# Blueshift_V4.net
KiCad netlist of a schematic drawn in EAGLE
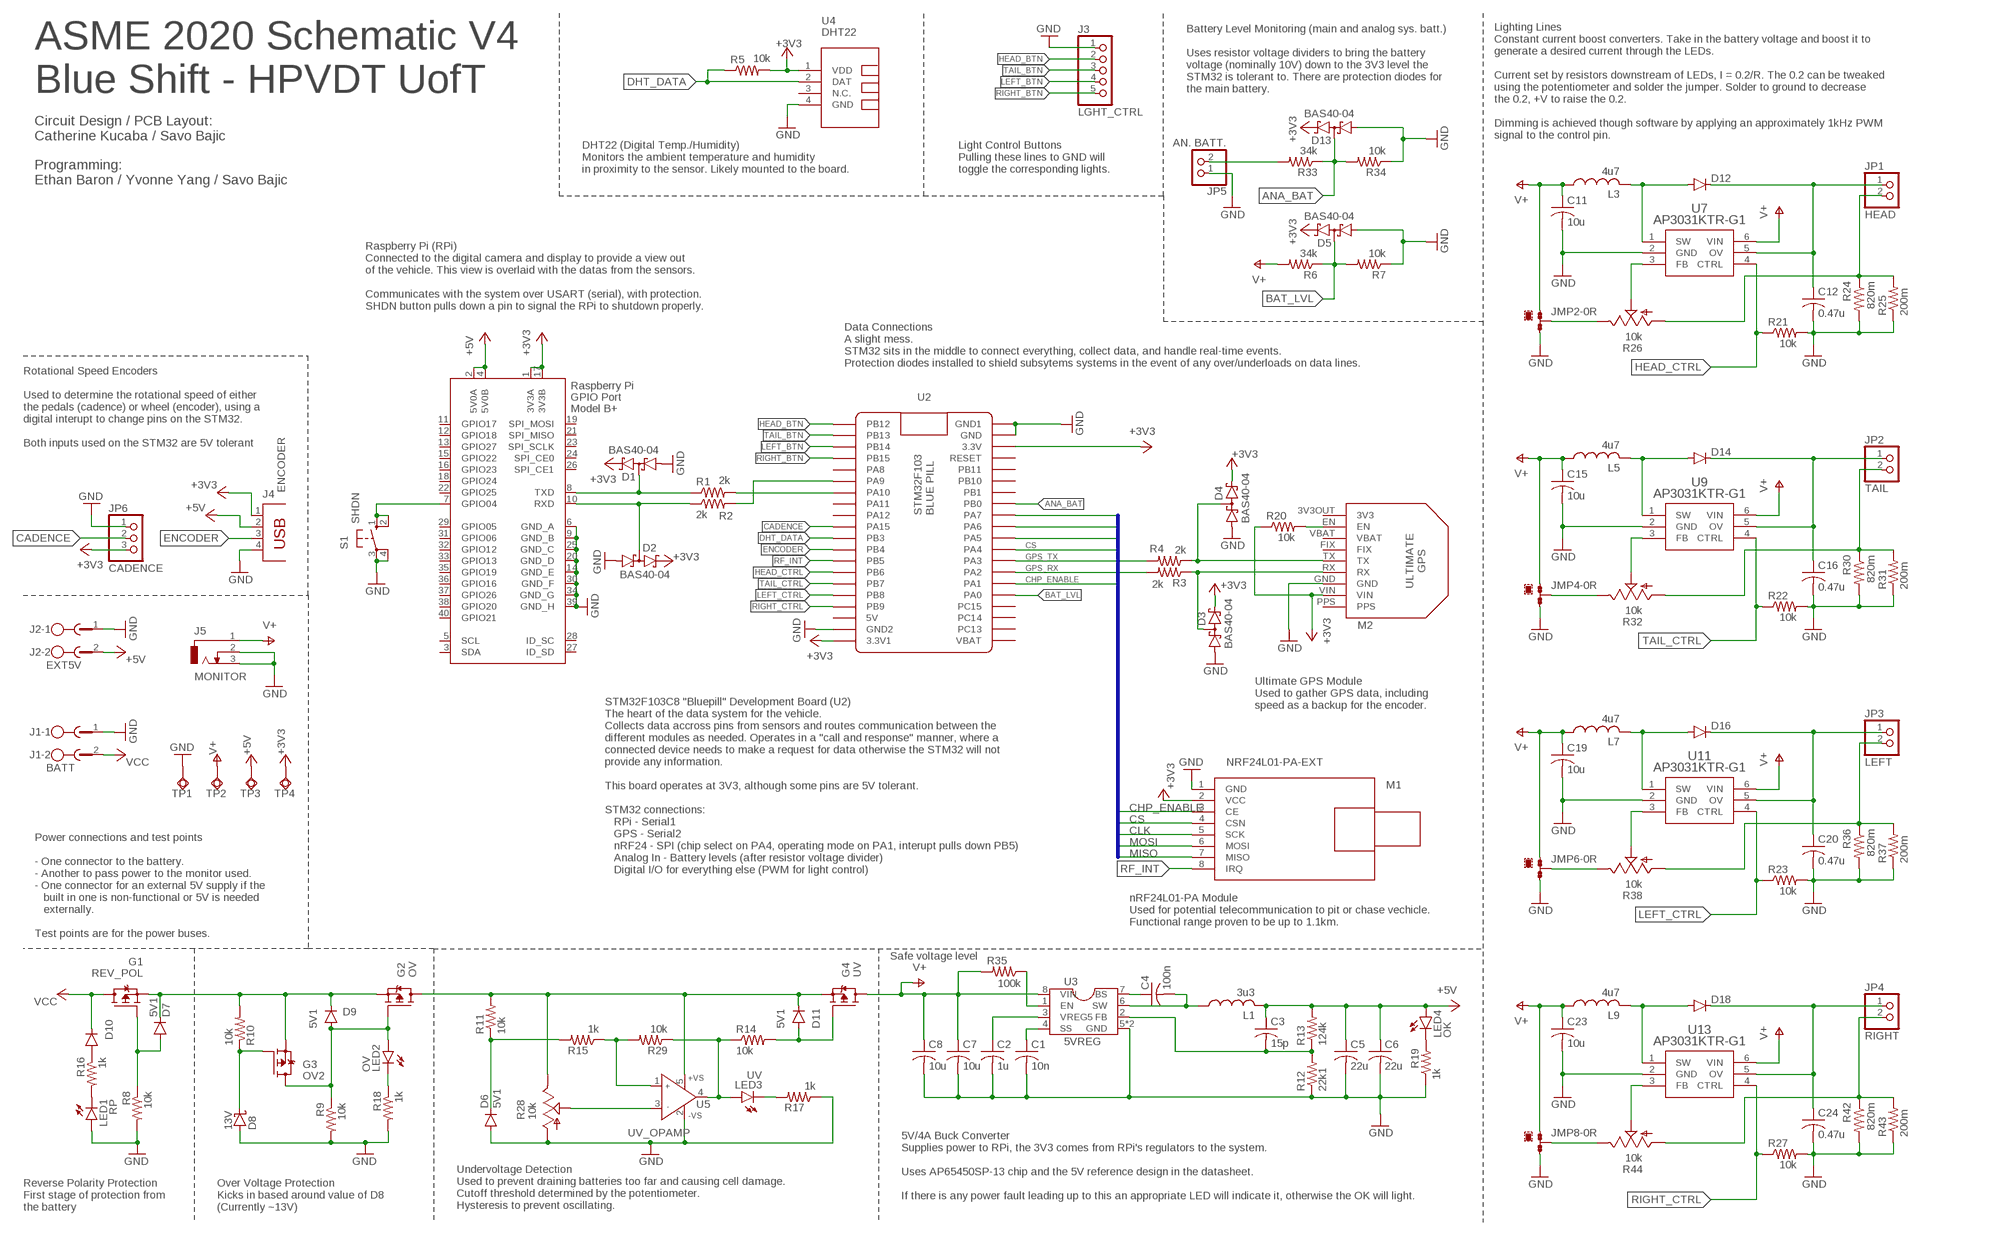
[diagram p0: schematic, sheet 1]

(export (version "E")
  (design (tool "Eeschema 10.0.6"))
  (components
    (comp (ref "C1")
      (value "10n")
      (footprint "eagle-import:C0402")
      (libsource (lib "eagle-import") (part "C-USC0402"))
    )
    (comp (ref "C2")
      (value "1u")
      (footprint "eagle-import:C0402")
      (libsource (lib "eagle-import") (part "C-USC0402"))
    )
    (comp (ref "C3")
      (value "15p")
      (footprint "eagle-import:C0402")
      (libsource (lib "eagle-import") (part "C-USC0402"))
    )
    (comp (ref "C4")
      (value "100n")
      (footprint "eagle-import:C0402")
      (libsource (lib "eagle-import") (part "C-USC0402"))
    )
    (comp (ref "C5")
      (value "22u")
      (footprint "eagle-import:C0805")
      (libsource (lib "eagle-import") (part "C-USC0805"))
    )
    (comp (ref "C6")
      (value "22u")
      (footprint "eagle-import:C0805")
      (libsource (lib "eagle-import") (part "C-USC0805"))
    )
    (comp (ref "C7")
      (value "10u")
      (footprint "eagle-import:C0805")
      (libsource (lib "eagle-import") (part "C-USC0805"))
    )
    (comp (ref "C8")
      (value "10u")
      (footprint "eagle-import:C0805")
      (libsource (lib "eagle-import") (part "C-USC0805"))
    )
    (comp (ref "C11")
      (value "10u")
      (footprint "eagle-import:C1206K")
      (libsource (lib "eagle-import") (part "C-USC1206K"))
    )
    (comp (ref "C12")
      (value "0.47u")
      (footprint "eagle-import:C1206K")
      (libsource (lib "eagle-import") (part "C-USC1206K"))
    )
    (comp (ref "C15")
      (value "10u")
      (footprint "eagle-import:C1206K")
      (libsource (lib "eagle-import") (part "C-USC1206K"))
    )
    (comp (ref "C16")
      (value "0.47u")
      (footprint "eagle-import:C1206K")
      (libsource (lib "eagle-import") (part "C-USC1206K"))
    )
    (comp (ref "C19")
      (value "10u")
      (footprint "eagle-import:C1206K")
      (libsource (lib "eagle-import") (part "C-USC1206K"))
    )
    (comp (ref "C20")
      (value "0.47u")
      (footprint "eagle-import:C1206K")
      (libsource (lib "eagle-import") (part "C-USC1206K"))
    )
    (comp (ref "C23")
      (value "10u")
      (footprint "eagle-import:C1206K")
      (libsource (lib "eagle-import") (part "C-USC1206K"))
    )
    (comp (ref "C24")
      (value "0.47u")
      (footprint "eagle-import:C1206K")
      (libsource (lib "eagle-import") (part "C-USC1206K"))
    )
    (comp (ref "D1")
      (value "BAS40-04")
      (footprint "eagle-import:SOT23")
      (libsource (lib "eagle-import") (part "BAS40-04"))
    )
    (comp (ref "D2")
      (value "BAS40-04")
      (footprint "eagle-import:SOT23")
      (libsource (lib "eagle-import") (part "BAS40-04"))
    )
    (comp (ref "D3")
      (value "BAS40-04")
      (footprint "eagle-import:SOT23")
      (libsource (lib "eagle-import") (part "BAS40-04"))
    )
    (comp (ref "D4")
      (value "BAS40-04")
      (footprint "eagle-import:SOT23")
      (libsource (lib "eagle-import") (part "BAS40-04"))
    )
    (comp (ref "D5")
      (value "BAS40-04")
      (footprint "eagle-import:SOT23")
      (libsource (lib "eagle-import") (part "BAS40-04"))
    )
    (comp (ref "D6")
      (value "5V1")
      (footprint "eagle-import:SOD323-R")
      (libsource (lib "eagle-import") (part "DIODE-SOD323-R"))
    )
    (comp (ref "D7")
      (value "5V1")
      (footprint "eagle-import:SOD323-R")
      (libsource (lib "eagle-import") (part "DIODE-SOD323-R"))
    )
    (comp (ref "D8")
      (value "13V")
      (footprint "eagle-import:SOT23")
      (libsource (lib "eagle-import") (part "BAS70"))
    )
    (comp (ref "D9")
      (value "5V1")
      (footprint "eagle-import:SOD323-R")
      (libsource (lib "eagle-import") (part "DIODE-SOD323-R"))
    )
    (comp (ref "D10")
      (value "DIODE-SOD80C")
      (footprint "eagle-import:SOD80C")
      (libsource (lib "eagle-import") (part "DIODE-SOD80C"))
    )
    (comp (ref "D11")
      (value "5V1")
      (footprint "eagle-import:SOD323-R")
      (libsource (lib "eagle-import") (part "DIODE-SOD323-R"))
    )
    (comp (ref "D12")
      (value "DIODE-DO-214AC")
      (footprint "eagle-import:DO-214AC")
      (libsource (lib "eagle-import") (part "DIODE-DO-214AC"))
    )
    (comp (ref "D13")
      (value "BAS40-04")
      (footprint "eagle-import:SOT23")
      (libsource (lib "eagle-import") (part "BAS40-04"))
    )
    (comp (ref "D14")
      (value "DIODE-DO-214AC")
      (footprint "eagle-import:DO-214AC")
      (libsource (lib "eagle-import") (part "DIODE-DO-214AC"))
    )
    (comp (ref "D16")
      (value "DIODE-DO-214AC")
      (footprint "eagle-import:DO-214AC")
      (libsource (lib "eagle-import") (part "DIODE-DO-214AC"))
    )
    (comp (ref "D18")
      (value "DIODE-DO-214AC")
      (footprint "eagle-import:DO-214AC")
      (libsource (lib "eagle-import") (part "DIODE-DO-214AC"))
    )
    (comp (ref "G1")
      (value "REV_POL")
      (footprint "eagle-import:TSOP-6")
      (libsource (lib "eagle-import") (part "SI3493DDV-T1-GE3"))
    )
    (comp (ref "G2")
      (value "OV")
      (footprint "eagle-import:TSOP-6")
      (libsource (lib "eagle-import") (part "SI3493DDV-T1-GE3"))
    )
    (comp (ref "G3")
      (value "OV2")
      (footprint "eagle-import:TSOP-6")
      (libsource (lib "eagle-import") (part "SI3493DDV-T1-GE3"))
    )
    (comp (ref "G4")
      (value "UV")
      (footprint "eagle-import:TSOP-6")
      (libsource (lib "eagle-import") (part "SI3493DDV-T1-GE3"))
    )
    (comp (ref "J1")
      (value "BATT")
      (footprint "eagle-import:MSTBV2")
      (libsource (lib "eagle-import") (part "MST2V"))
    )
    (comp (ref "J2")
      (value "EXT5V")
      (footprint "eagle-import:MSTBV2")
      (libsource (lib "eagle-import") (part "MST2V"))
    )
    (comp (ref "J3")
      (value "LGHT_CTRL")
      (footprint "eagle-import:1X05")
      (libsource (lib "eagle-import") (part "PINHD-1X5"))
    )
    (comp (ref "J4")
      (value "ENCODER")
      (footprint "eagle-import:PN87520")
      (libsource (lib "eagle-import") (part "PN87520"))
    )
    (comp (ref "J5")
      (value "MONITOR")
      (footprint "eagle-import:DCJ0303")
      (libsource (lib "eagle-import") (part "DCJ0303"))
    )
    (comp (ref "JMP2")
      (value "0R-JUMPA")
      (footprint "eagle-import:A0R-JMP")
      (libsource (lib "eagle-import") (part "0R-JUMPA"))
    )
    (comp (ref "JMP4")
      (value "0R-JUMPA")
      (footprint "eagle-import:A0R-JMP")
      (libsource (lib "eagle-import") (part "0R-JUMPA"))
    )
    (comp (ref "JMP6")
      (value "0R-JUMPA")
      (footprint "eagle-import:A0R-JMP")
      (libsource (lib "eagle-import") (part "0R-JUMPA"))
    )
    (comp (ref "JMP8")
      (value "0R-JUMPA")
      (footprint "eagle-import:A0R-JMP")
      (libsource (lib "eagle-import") (part "0R-JUMPA"))
    )
    (comp (ref "JP1")
      (value "HEAD")
      (footprint "eagle-import:1X02")
      (libsource (lib "eagle-import") (part "PINHD-1X2"))
    )
    (comp (ref "JP2")
      (value "TAIL")
      (footprint "eagle-import:1X02")
      (libsource (lib "eagle-import") (part "PINHD-1X2"))
    )
    (comp (ref "JP3")
      (value "LEFT")
      (footprint "eagle-import:1X02")
      (libsource (lib "eagle-import") (part "PINHD-1X2"))
    )
    (comp (ref "JP4")
      (value "RIGHT")
      (footprint "eagle-import:1X02")
      (libsource (lib "eagle-import") (part "PINHD-1X2"))
    )
    (comp (ref "JP5")
      (value "AN. BATT.")
      (footprint "eagle-import:1X02")
      (libsource (lib "eagle-import") (part "PINHD-1X2"))
    )
    (comp (ref "JP6")
      (value "CADENCE")
      (footprint "eagle-import:1X03")
      (libsource (lib "eagle-import") (part "PINHD-1X3"))
    )
    (comp (ref "L1")
      (value "3u3")
      (footprint "eagle-import:SDES064T")
      (libsource (lib "eagle-import") (part "SDES064T-3R3MS"))
    )
    (comp (ref "L3")
      (value "4u7")
      (footprint "eagle-import:INDDFN600X600X280-2N")
      (libsource (lib "eagle-import") (part "NR6028NR6028"))
    )
    (comp (ref "L5")
      (value "4u7")
      (footprint "eagle-import:INDDFN600X600X280-2N")
      (libsource (lib "eagle-import") (part "NR6028NR6028"))
    )
    (comp (ref "L7")
      (value "4u7")
      (footprint "eagle-import:INDDFN600X600X280-2N")
      (libsource (lib "eagle-import") (part "NR6028NR6028"))
    )
    (comp (ref "L9")
      (value "4u7")
      (footprint "eagle-import:INDDFN600X600X280-2N")
      (libsource (lib "eagle-import") (part "NR6028NR6028"))
    )
    (comp (ref "LED1")
      (value "RP")
      (footprint "eagle-import:SML0805")
      (libsource (lib "eagle-import") (part "LEDSML0805"))
    )
    (comp (ref "LED2")
      (value "OV")
      (footprint "eagle-import:SML0805")
      (libsource (lib "eagle-import") (part "LEDSML0805"))
    )
    (comp (ref "LED3")
      (value "UV")
      (footprint "eagle-import:SML0805")
      (libsource (lib "eagle-import") (part "LEDSML0805"))
    )
    (comp (ref "LED4")
      (value "OK")
      (footprint "eagle-import:SML0805")
      (libsource (lib "eagle-import") (part "LEDSML0805"))
    )
    (comp (ref "M1")
      (value "NRF24L01-PA-EXT")
      (footprint "eagle-import:WIRELESS-NRF24L01-PA-EXT")
      (libsource (lib "eagle-import") (part "WIRELESS-NRF24L01-PA-EXT"))
    )
    (comp (ref "M2")
      (value "ULTIMATE-GPS")
      (footprint "eagle-import:ULTIMATE_GPS")
      (libsource (lib "eagle-import") (part "ULTIMATE-GPS"))
    )
    (comp (ref "R1")
      (value "2k")
      (footprint "eagle-import:R0402")
      (libsource (lib "eagle-import") (part "R-US_R0402"))
    )
    (comp (ref "R2")
      (value "2k")
      (footprint "eagle-import:R0402")
      (libsource (lib "eagle-import") (part "R-US_R0402"))
    )
    (comp (ref "R3")
      (value "2k")
      (footprint "eagle-import:R0402")
      (libsource (lib "eagle-import") (part "R-US_R0402"))
    )
    (comp (ref "R4")
      (value "2k")
      (footprint "eagle-import:R0402")
      (libsource (lib "eagle-import") (part "R-US_R0402"))
    )
    (comp (ref "R5")
      (value "10k")
      (footprint "eagle-import:R0402")
      (libsource (lib "eagle-import") (part "R-US_R0402"))
    )
    (comp (ref "R6")
      (value "34k")
      (footprint "eagle-import:R0402")
      (libsource (lib "eagle-import") (part "R-US_R0402"))
    )
    (comp (ref "R7")
      (value "10k")
      (footprint "eagle-import:R0402")
      (libsource (lib "eagle-import") (part "R-US_R0402"))
    )
    (comp (ref "R8")
      (value "10k")
      (footprint "eagle-import:R0402")
      (libsource (lib "eagle-import") (part "R-US_R0402"))
    )
    (comp (ref "R9")
      (value "10k")
      (footprint "eagle-import:R0402")
      (libsource (lib "eagle-import") (part "R-US_R0402"))
    )
    (comp (ref "R10")
      (value "10k")
      (footprint "eagle-import:R0402")
      (libsource (lib "eagle-import") (part "R-US_R0402"))
    )
    (comp (ref "R11")
      (value "10k")
      (footprint "eagle-import:R0402")
      (libsource (lib "eagle-import") (part "R-US_R0402"))
    )
    (comp (ref "R12")
      (value "22k1")
      (footprint "eagle-import:R0402")
      (libsource (lib "eagle-import") (part "R-US_R0402"))
    )
    (comp (ref "R13")
      (value "124k")
      (footprint "eagle-import:R0402")
      (libsource (lib "eagle-import") (part "R-US_R0402"))
    )
    (comp (ref "R14")
      (value "10k")
      (footprint "eagle-import:R0402")
      (libsource (lib "eagle-import") (part "R-US_R0402"))
    )
    (comp (ref "R15")
      (value "1k")
      (footprint "eagle-import:R0402")
      (libsource (lib "eagle-import") (part "R-US_R0402"))
    )
    (comp (ref "R16")
      (value "1k")
      (footprint "eagle-import:R0402")
      (libsource (lib "eagle-import") (part "R-US_R0402"))
    )
    (comp (ref "R17")
      (value "1k")
      (footprint "eagle-import:R0402")
      (libsource (lib "eagle-import") (part "R-US_R0402"))
    )
    (comp (ref "R18")
      (value "1k")
      (footprint "eagle-import:R0402")
      (libsource (lib "eagle-import") (part "R-US_R0402"))
    )
    (comp (ref "R19")
      (value "1k")
      (footprint "eagle-import:R0402")
      (libsource (lib "eagle-import") (part "R-US_R0402"))
    )
    (comp (ref "R20")
      (value "10k")
      (footprint "eagle-import:R0402")
      (libsource (lib "eagle-import") (part "R-US_R0402"))
    )
    (comp (ref "R21")
      (value "10k")
      (footprint "eagle-import:R0402")
      (libsource (lib "eagle-import") (part "R-US_R0402"))
    )
    (comp (ref "R22")
      (value "10k")
      (footprint "eagle-import:R0402")
      (libsource (lib "eagle-import") (part "R-US_R0402"))
    )
    (comp (ref "R23")
      (value "10k")
      (footprint "eagle-import:R0402")
      (libsource (lib "eagle-import") (part "R-US_R0402"))
    )
    (comp (ref "R24")
      (value "820m")
      (footprint "eagle-import:R0603")
      (libsource (lib "eagle-import") (part "R-US_R0603"))
    )
    (comp (ref "R25")
      (value "200m")
      (footprint "eagle-import:R0805")
      (libsource (lib "eagle-import") (part "R-US_R0805"))
    )
    (comp (ref "R26")
      (value "10k")
      (footprint "eagle-import:RJ9W")
      (libsource (lib "eagle-import") (part "TRIM_US-RJ9W"))
    )
    (comp (ref "R27")
      (value "10k")
      (footprint "eagle-import:R0402")
      (libsource (lib "eagle-import") (part "R-US_R0402"))
    )
    (comp (ref "R28")
      (value "10k")
      (footprint "eagle-import:RJ9W")
      (libsource (lib "eagle-import") (part "TRIM_US-RJ9W"))
    )
    (comp (ref "R29")
      (value "10k")
      (footprint "eagle-import:R0402")
      (libsource (lib "eagle-import") (part "R-US_R0402"))
    )
    (comp (ref "R30")
      (value "820m")
      (footprint "eagle-import:R0603")
      (libsource (lib "eagle-import") (part "R-US_R0603"))
    )
    (comp (ref "R31")
      (value "200m")
      (footprint "eagle-import:R0805")
      (libsource (lib "eagle-import") (part "R-US_R0805"))
    )
    (comp (ref "R32")
      (value "10k")
      (footprint "eagle-import:RJ9W")
      (libsource (lib "eagle-import") (part "TRIM_US-RJ9W"))
    )
    (comp (ref "R33")
      (value "34k")
      (footprint "eagle-import:R0402")
      (libsource (lib "eagle-import") (part "R-US_R0402"))
    )
    (comp (ref "R34")
      (value "10k")
      (footprint "eagle-import:R0402")
      (libsource (lib "eagle-import") (part "R-US_R0402"))
    )
    (comp (ref "R35")
      (value "100k")
      (footprint "eagle-import:R0402")
      (libsource (lib "eagle-import") (part "R-US_R0402"))
    )
    (comp (ref "R36")
      (value "820m")
      (footprint "eagle-import:R0603")
      (libsource (lib "eagle-import") (part "R-US_R0603"))
    )
    (comp (ref "R37")
      (value "200m")
      (footprint "eagle-import:R0805")
      (libsource (lib "eagle-import") (part "R-US_R0805"))
    )
    (comp (ref "R38")
      (value "10k")
      (footprint "eagle-import:RJ9W")
      (libsource (lib "eagle-import") (part "TRIM_US-RJ9W"))
    )
    (comp (ref "R42")
      (value "820m")
      (footprint "eagle-import:R0603")
      (libsource (lib "eagle-import") (part "R-US_R0603"))
    )
    (comp (ref "R43")
      (value "200m")
      (footprint "eagle-import:R0805")
      (libsource (lib "eagle-import") (part "R-US_R0805"))
    )
    (comp (ref "R44")
      (value "10k")
      (footprint "eagle-import:RJ9W")
      (libsource (lib "eagle-import") (part "TRIM_US-RJ9W"))
    )
    (comp (ref "S1")
      (value "SHDN")
      (footprint "eagle-import:B3F-10XX")
      (fields (field (name "MPN") "B3F-1000"))
      (libsource (lib "eagle-import") (part "10-XX"))
    )
    (comp (ref "TP1")
      (value "TPSQTP20SQ")
      (footprint "eagle-import:TP20SQ")
      (libsource (lib "eagle-import") (part "TPSQTP20SQ"))
    )
    (comp (ref "TP2")
      (value "TPSQTP20R")
      (footprint "eagle-import:TP20R")
      (libsource (lib "eagle-import") (part "TPSQTP20R"))
    )
    (comp (ref "TP3")
      (value "TPSQTP20R")
      (footprint "eagle-import:TP20R")
      (libsource (lib "eagle-import") (part "TPSQTP20R"))
    )
    (comp (ref "TP4")
      (value "TPSQTP20R")
      (footprint "eagle-import:TP20R")
      (libsource (lib "eagle-import") (part "TPSQTP20R"))
    )
    (comp (ref "U1")
      (value "RASPI_HAT")
      (footprint "eagle-import:RASPI_BOARD_B+HAT_CF")
      (libsource (lib "eagle-import") (part "RASPI_HAT"))
    )
    (comp (ref "U2")
      (value "BLUEPILL")
      (footprint "eagle-import:BLUE_PILL")
      (libsource (lib "eagle-import") (part "BLUE_PILL"))
    )
    (comp (ref "U3")
      (value "5VREG")
      (footprint "eagle-import:SO-8EP")
      (libsource (lib "eagle-import") (part "AP65450SP-13"))
    )
    (comp (ref "U4")
      (value "DHT22")
      (footprint "eagle-import:TEMP-HUM-SENSOR-DHT22")
      (libsource (lib "eagle-import") (part "TEMP-HUM-SENSOR-DHT22"))
    )
    (comp (ref "U5")
      (value "UV_OPAMP")
      (footprint "eagle-import:SOT-753")
      (libsource (lib "eagle-import") (part "TA75S558F,LF"))
    )
    (comp (ref "U7")
      (value "AP3031KTR-G1")
      (footprint "eagle-import:SOT23-6")
      (fields (field (name "MANUFACTURER_PART_NUMBER") "AP3031KTRG1"))
      (libsource (lib "eagle-import") (part "AP3031KTR-G1"))
    )
    (comp (ref "U9")
      (value "AP3031KTR-G1")
      (footprint "eagle-import:SOT23-6")
      (fields (field (name "MANUFACTURER_PART_NUMBER") "AP3031KTRG1"))
      (libsource (lib "eagle-import") (part "AP3031KTR-G1"))
    )
    (comp (ref "U11")
      (value "AP3031KTR-G1")
      (footprint "eagle-import:SOT23-6")
      (fields (field (name "MANUFACTURER_PART_NUMBER") "AP3031KTRG1"))
      (libsource (lib "eagle-import") (part "AP3031KTR-G1"))
    )
    (comp (ref "U13")
      (value "AP3031KTR-G1")
      (footprint "eagle-import:SOT23-6")
      (fields (field (name "MANUFACTURER_PART_NUMBER") "AP3031KTRG1"))
      (libsource (lib "eagle-import") (part "AP3031KTR-G1"))
    )
  )
  (nets
    (net (code "1") (name "+3V3") (class "Default")
      (node (ref "D1") (pin "2") (pinfunction "C2_2") (pintype "passive"))
      (node (ref "D13") (pin "2") (pinfunction "C2_2") (pintype "passive"))
      (node (ref "D2") (pin "2") (pinfunction "C2_2") (pintype "passive"))
      (node (ref "D3") (pin "2") (pinfunction "C2_2") (pintype "passive"))
      (node (ref "D4") (pin "2") (pinfunction "C2_2") (pintype "passive"))
      (node (ref "D5") (pin "2") (pinfunction "C2_2") (pintype "passive"))
      (node (ref "J4") (pin "1") (pinfunction "1_1") (pintype "passive"))
      (node (ref "JP6") (pin "3") (pinfunction "3_3") (pintype "passive"))
      (node (ref "M1") (pin "2") (pinfunction "VCC_2") (pintype "power_in"))
      (node (ref "M2") (pin "VIN") (pinfunction "VIN_VIN") (pintype "power_in"))
      (node (ref "R20") (pin "1") (pinfunction "1_1") (pintype "passive"))
      (node (ref "R5") (pin "2") (pinfunction "2_2") (pintype "passive"))
      (node (ref "TP4") (pin "TP") (pinfunction "TP_TP") (pintype "input"))
      (node (ref "U1") (pin "1") (pinfunction "3V3A_1") (pintype "power_in"))
      (node (ref "U1") (pin "17") (pinfunction "3V3B_17") (pintype "power_in"))
      (node (ref "U2") (pin "P$20") (pinfunction "3.3V1_P$20") (pintype "bidirectional"))
      (node (ref "U2") (pin "P$23") (pinfunction "3.3V_P$23") (pintype "bidirectional"))
      (node (ref "U4") (pin "1") (pinfunction "VDD_1") (pintype "power_in"))
    )
    (net (code "2") (name "+5V") (class "Default")
      (node (ref "C3") (pin "1") (pinfunction "1_1") (pintype "passive"))
      (node (ref "C5") (pin "1") (pinfunction "1_1") (pintype "passive"))
      (node (ref "C6") (pin "1") (pinfunction "1_1") (pintype "passive"))
      (node (ref "J2") (pin "2") (pinfunction "1_2") (pintype "passive"))
      (node (ref "J4") (pin "2") (pinfunction "2_2") (pintype "passive"))
      (node (ref "L1") (pin "2") (pinfunction "2_2") (pintype "passive"))
      (node (ref "LED4") (pin "A") (pinfunction "A_A") (pintype "passive"))
      (node (ref "R13") (pin "2") (pinfunction "2_2") (pintype "passive"))
      (node (ref "TP3") (pin "TP") (pinfunction "TP_TP") (pintype "input"))
      (node (ref "U1") (pin "2") (pinfunction "5V0A_2") (pintype "power_in"))
      (node (ref "U1") (pin "4") (pinfunction "5V0B_4") (pintype "power_in"))
    )
    (net (code "3") (name "/CHP_ENABLE") (class "Default")
      (node (ref "M1") (pin "3") (pinfunction "CE_3") (pintype "bidirectional"))
      (node (ref "U2") (pin "P$35") (pinfunction "PA1_P$35") (pintype "bidirectional"))
    )
    (net (code "4") (name "/CLK") (class "Default")
      (node (ref "M1") (pin "5") (pinfunction "SCK_5") (pintype "bidirectional"))
      (node (ref "U2") (pin "P$31") (pinfunction "PA5_P$31") (pintype "bidirectional"))
    )
    (net (code "5") (name "/CS") (class "Default")
      (node (ref "M1") (pin "4") (pinfunction "CSN_4") (pintype "bidirectional"))
      (node (ref "U2") (pin "P$32") (pinfunction "PA4_P$32") (pintype "bidirectional"))
    )
    (net (code "6") (name "/GPS_RX") (class "Default")
      (node (ref "R3") (pin "2") (pinfunction "2_2") (pintype "passive"))
      (node (ref "U2") (pin "P$34") (pinfunction "PA2_P$34") (pintype "bidirectional"))
    )
    (net (code "7") (name "/GPS_TX") (class "Default")
      (node (ref "R4") (pin "2") (pinfunction "2_2") (pintype "passive"))
      (node (ref "U2") (pin "P$33") (pinfunction "PA3_P$33") (pintype "bidirectional"))
    )
    (net (code "8") (name "/MISO") (class "Default")
      (node (ref "M1") (pin "7") (pinfunction "MISO_7") (pintype "bidirectional"))
      (node (ref "U2") (pin "P$30") (pinfunction "PA6_P$30") (pintype "bidirectional"))
    )
    (net (code "9") (name "/MOSI") (class "Default")
      (node (ref "M1") (pin "6") (pinfunction "MOSI_6") (pintype "bidirectional"))
      (node (ref "U2") (pin "P$29") (pinfunction "PA7_P$29") (pintype "bidirectional"))
    )
    (net (code "10") (name "ANA_BAT") (class "Default")
      (node (ref "D13") (pin "3") (pinfunction "C1A2_3") (pintype "passive"))
      (node (ref "R33") (pin "1") (pinfunction "1_1") (pintype "passive"))
      (node (ref "R34") (pin "2") (pinfunction "2_2") (pintype "passive"))
      (node (ref "U2") (pin "P$28") (pinfunction "PB0_P$28") (pintype "bidirectional"))
    )
    (net (code "11") (name "BAT_LVL") (class "Default")
      (node (ref "D5") (pin "3") (pinfunction "C1A2_3") (pintype "passive"))
      (node (ref "R6") (pin "1") (pinfunction "1_1") (pintype "passive"))
      (node (ref "R7") (pin "2") (pinfunction "2_2") (pintype "passive"))
      (node (ref "U2") (pin "P$36") (pinfunction "PA0_P$36") (pintype "bidirectional"))
    )
    (net (code "12") (name "CADENCE") (class "Default")
      (node (ref "JP6") (pin "2") (pinfunction "2_2") (pintype "passive"))
      (node (ref "U2") (pin "P$10") (pinfunction "PA15_P$10") (pintype "bidirectional"))
    )
    (net (code "13") (name "DHT_DATA") (class "Default")
      (node (ref "R5") (pin "1") (pinfunction "1_1") (pintype "passive"))
      (node (ref "U2") (pin "P$11") (pinfunction "PB3_P$11") (pintype "bidirectional"))
      (node (ref "U4") (pin "2") (pinfunction "DAT_2") (pintype "bidirectional"))
    )
    (net (code "14") (name "ENCODER") (class "Default")
      (node (ref "J4") (pin "3") (pinfunction "3_3") (pintype "passive"))
      (node (ref "U2") (pin "P$12") (pinfunction "PB4_P$12") (pintype "bidirectional"))
    )
    (net (code "15") (name "GND") (class "Default")
      (node (ref "C1") (pin "2") (pinfunction "2_2") (pintype "passive"))
      (node (ref "C11") (pin "2") (pinfunction "2_2") (pintype "passive"))
      (node (ref "C12") (pin "2") (pinfunction "2_2") (pintype "passive"))
      (node (ref "C15") (pin "2") (pinfunction "2_2") (pintype "passive"))
      (node (ref "C16") (pin "2") (pinfunction "2_2") (pintype "passive"))
      (node (ref "C19") (pin "2") (pinfunction "2_2") (pintype "passive"))
      (node (ref "C2") (pin "2") (pinfunction "2_2") (pintype "passive"))
      (node (ref "C20") (pin "2") (pinfunction "2_2") (pintype "passive"))
      (node (ref "C23") (pin "2") (pinfunction "2_2") (pintype "passive"))
      (node (ref "C24") (pin "2") (pinfunction "2_2") (pintype "passive"))
      (node (ref "C5") (pin "2") (pinfunction "2_2") (pintype "passive"))
      (node (ref "C6") (pin "2") (pinfunction "2_2") (pintype "passive"))
      (node (ref "C7") (pin "2") (pinfunction "2_2") (pintype "passive"))
      (node (ref "C8") (pin "2") (pinfunction "2_2") (pintype "passive"))
      (node (ref "D1") (pin "1") (pinfunction "A1_1") (pintype "passive"))
      (node (ref "D13") (pin "1") (pinfunction "A1_1") (pintype "passive"))
      (node (ref "D2") (pin "1") (pinfunction "A1_1") (pintype "passive"))
      (node (ref "D3") (pin "1") (pinfunction "A1_1") (pintype "passive"))
      (node (ref "D4") (pin "1") (pinfunction "A1_1") (pintype "passive"))
      (node (ref "D5") (pin "1") (pinfunction "A1_1") (pintype "passive"))
      (node (ref "D6") (pin "A") (pinfunction "A_A") (pintype "passive"))
      (node (ref "D8") (pin "1") (pinfunction "A_1") (pintype "passive"))
      (node (ref "J1") (pin "1") (pinfunction "1_1") (pintype "passive"))
      (node (ref "J2") (pin "1") (pinfunction "1_1") (pintype "passive"))
      (node (ref "J3") (pin "1") (pinfunction "1_1") (pintype "passive"))
      (node (ref "J4") (pin "4") (pinfunction "4_4") (pintype "passive"))
      (node (ref "J5") (pin "2") (pinfunction "2_2") (pintype "passive"))
      (node (ref "J5") (pin "3") (pinfunction "3_3") (pintype "passive"))
      (node (ref "JMP2") (pin "3") (pinfunction "3_3") (pintype "passive"))
      (node (ref "JMP4") (pin "3") (pinfunction "3_3") (pintype "passive"))
      (node (ref "JMP6") (pin "3") (pinfunction "3_3") (pintype "passive"))
      (node (ref "JMP8") (pin "3") (pinfunction "3_3") (pintype "passive"))
      (node (ref "JP5") (pin "1") (pinfunction "1_1") (pintype "passive"))
      (node (ref "JP6") (pin "1") (pinfunction "1_1") (pintype "passive"))
      (node (ref "LED1") (pin "A") (pinfunction "A_A") (pintype "passive"))
      (node (ref "M1") (pin "1") (pinfunction "GND_1") (pintype "power_in"))
      (node (ref "M2") (pin "GND") (pinfunction "GND_GND") (pintype "power_in"))
      (node (ref "R12") (pin "1") (pinfunction "1_1") (pintype "passive"))
      (node (ref "R17") (pin "1") (pinfunction "1_1") (pintype "passive"))
      (node (ref "R18") (pin "2") (pinfunction "2_2") (pintype "passive"))
      (node (ref "R19") (pin "1") (pinfunction "1_1") (pintype "passive"))
      (node (ref "R21") (pin "2") (pinfunction "2_2") (pintype "passive"))
      (node (ref "R22") (pin "2") (pinfunction "2_2") (pintype "passive"))
      (node (ref "R23") (pin "2") (pinfunction "2_2") (pintype "passive"))
      (node (ref "R24") (pin "2") (pinfunction "2_2") (pintype "passive"))
      (node (ref "R25") (pin "1") (pinfunction "1_1") (pintype "passive"))
      (node (ref "R27") (pin "2") (pinfunction "2_2") (pintype "passive"))
      (node (ref "R28") (pin "A") (pinfunction "A_A") (pintype "passive"))
      (node (ref "R30") (pin "2") (pinfunction "2_2") (pintype "passive"))
      (node (ref "R31") (pin "1") (pinfunction "1_1") (pintype "passive"))
      (node (ref "R34") (pin "1") (pinfunction "1_1") (pintype "passive"))
      (node (ref "R36") (pin "2") (pinfunction "2_2") (pintype "passive"))
      (node (ref "R37") (pin "1") (pinfunction "1_1") (pintype "passive"))
      (node (ref "R42") (pin "2") (pinfunction "2_2") (pintype "passive"))
      (node (ref "R43") (pin "1") (pinfunction "1_1") (pintype "passive"))
      (node (ref "R7") (pin "1") (pinfunction "1_1") (pintype "passive"))
      (node (ref "R8") (pin "2") (pinfunction "2_2") (pintype "passive"))
      (node (ref "R9") (pin "2") (pinfunction "2_2") (pintype "passive"))
      (node (ref "S1") (pin "3") (pinfunction "P_3") (pintype "passive"))
      (node (ref "S1") (pin "4") (pinfunction "P1_4") (pintype "passive"))
      (node (ref "TP1") (pin "TP") (pinfunction "TP_TP") (pintype "input"))
      (node (ref "U1") (pin "14") (pinfunction "GND_E_14") (pintype "power_in"))
      (node (ref "U1") (pin "20") (pinfunction "GND_D_20") (pintype "power_in"))
      (node (ref "U1") (pin "25") (pinfunction "GND_C_25") (pintype "power_in"))
      (node (ref "U1") (pin "30") (pinfunction "GND_F_30") (pintype "power_in"))
      (node (ref "U1") (pin "34") (pinfunction "GND_G_34") (pintype "power_in"))
      (node (ref "U1") (pin "39") (pinfunction "GND_H_39") (pintype "power_in"))
      (node (ref "U1") (pin "6") (pinfunction "GND_A_6") (pintype "power_in"))
      (node (ref "U1") (pin "9") (pinfunction "GND_B_9") (pintype "power_in"))
      (node (ref "U11") (pin "2") (pinfunction "GND_2") (pintype "power_in"))
      (node (ref "U13") (pin "2") (pinfunction "GND_2") (pintype "power_in"))
      (node (ref "U2") (pin "P$19") (pinfunction "GND2_P$19") (pintype "bidirectional"))
      (node (ref "U2") (pin "P$21") (pinfunction "GND1_P$21") (pintype "power_in"))
      (node (ref "U2") (pin "P$22") (pinfunction "GND_P$22") (pintype "bidirectional"))
      (node (ref "U3") (pin "5") (pinfunction "GND_5") (pintype "bidirectional"))
      (node (ref "U3") (pin "TP") (pinfunction "GND_TP") (pintype "bidirectional"))
      (node (ref "U4") (pin "4") (pinfunction "GND_4") (pintype "power_in"))
      (node (ref "U5") (pin "2") (pinfunction "-VS_2") (pintype "input"))
      (node (ref "U7") (pin "2") (pinfunction "GND_2") (pintype "power_in"))
      (node (ref "U9") (pin "2") (pinfunction "GND_2") (pintype "power_in"))
    )
    (net (code "16") (name "HEAD_BTN") (class "Default")
      (node (ref "J3") (pin "2") (pinfunction "2_2") (pintype "passive"))
      (node (ref "U2") (pin "P$1") (pinfunction "PB12_P$1") (pintype "bidirectional"))
    )
    (net (code "17") (name "HEAD_CTRL") (class "Default")
      (node (ref "R21") (pin "1") (pinfunction "1_1") (pintype "passive"))
      (node (ref "U2") (pin "P$14") (pinfunction "PB6_P$14") (pintype "bidirectional"))
      (node (ref "U7") (pin "4") (pinfunction "CTRL_4") (pintype "passive"))
    )
    (net (code "18") (name "LEFT_BTN") (class "Default")
      (node (ref "J3") (pin "4") (pinfunction "4_4") (pintype "passive"))
      (node (ref "U2") (pin "P$3") (pinfunction "PB14_P$3") (pintype "bidirectional"))
    )
    (net (code "19") (name "LEFT_CTRL") (class "Default")
      (node (ref "R23") (pin "1") (pinfunction "1_1") (pintype "passive"))
      (node (ref "U11") (pin "4") (pinfunction "CTRL_4") (pintype "passive"))
      (node (ref "U2") (pin "P$16") (pinfunction "PB8_P$16") (pintype "bidirectional"))
    )
    (net (code "20") (name "Net-(D1-C1A2)") (class "Default")
      (node (ref "D1") (pin "3") (pinfunction "C1A2_3") (pintype "passive"))
      (node (ref "R1") (pin "1") (pinfunction "1_1") (pintype "passive"))
      (node (ref "U1") (pin "8") (pinfunction "TXD_8") (pintype "bidirectional"))
    )
    (net (code "21") (name "Net-(D2-C1A2)") (class "Default")
      (node (ref "D2") (pin "3") (pinfunction "C1A2_3") (pintype "passive"))
      (node (ref "R2") (pin "1") (pinfunction "1_1") (pintype "passive"))
      (node (ref "U1") (pin "10") (pinfunction "RXD_10") (pintype "bidirectional"))
    )
    (net (code "22") (name "Net-(D3-C1A2)") (class "Default")
      (node (ref "D3") (pin "3") (pinfunction "C1A2_3") (pintype "passive"))
      (node (ref "M2") (pin "RX") (pinfunction "RX_RX") (pintype "input"))
      (node (ref "R3") (pin "1") (pinfunction "1_1") (pintype "passive"))
    )
    (net (code "23") (name "Net-(D4-C1A2)") (class "Default")
      (node (ref "D4") (pin "3") (pinfunction "C1A2_3") (pintype "passive"))
      (node (ref "M2") (pin "TX") (pinfunction "TX_TX") (pintype "output"))
      (node (ref "R4") (pin "1") (pinfunction "1_1") (pintype "passive"))
    )
    (net (code "24") (name "Net-(D6-PadC)") (class "Default")
      (node (ref "D6") (pin "C") (pinfunction "C_C") (pintype "passive"))
      (node (ref "R11") (pin "1") (pinfunction "1_1") (pintype "passive"))
      (node (ref "R15") (pin "2") (pinfunction "2_2") (pintype "passive"))
    )
    (net (code "25") (name "Net-(D8-C)") (class "Default")
      (node (ref "D8") (pin "3") (pinfunction "C_3") (pintype "passive"))
      (node (ref "G3") (pin "3") (pinfunction "G_3") (pintype "passive"))
      (node (ref "R10") (pin "1") (pinfunction "1_1") (pintype "passive"))
    )
    (net (code "26") (name "Net-(D10-PadA)") (class "Default")
      (node (ref "D10") (pin "A") (pinfunction "A_A") (pintype "passive"))
      (node (ref "R16") (pin "1") (pinfunction "1_1") (pintype "passive"))
    )
    (net (code "27") (name "Net-(G1-G)") (class "Default")
      (node (ref "D7") (pin "A") (pinfunction "A_A") (pintype "passive"))
      (node (ref "G1") (pin "3") (pinfunction "G_3") (pintype "passive"))
      (node (ref "R8") (pin "1") (pinfunction "1_1") (pintype "passive"))
    )
    (net (code "28") (name "Net-(G1-S)") (class "Default")
      (node (ref "D7") (pin "C") (pinfunction "C_C") (pintype "passive"))
      (node (ref "D9") (pin "C") (pinfunction "C_C") (pintype "passive"))
      (node (ref "G1") (pin "4") (pinfunction "S_4") (pintype "passive"))
      (node (ref "G2") (pin "4") (pinfunction "S_4") (pintype "passive"))
      (node (ref "G3") (pin "4") (pinfunction "S_4") (pintype "passive"))
      (node (ref "R10") (pin "2") (pinfunction "2_2") (pintype "passive"))
    )
    (net (code "29") (name "Net-(G2-G)") (class "Default")
      (node (ref "D9") (pin "A") (pinfunction "A_A") (pintype "passive"))
      (node (ref "G2") (pin "3") (pinfunction "G_3") (pintype "passive"))
      (node (ref "G3") (pin "1") (pinfunction "D_1") (pintype "passive"))
      (node (ref "G3") (pin "2") (pinfunction "D_2") (pintype "passive"))
      (node (ref "G3") (pin "5") (pinfunction "D_5") (pintype "passive"))
      (node (ref "G3") (pin "6") (pinfunction "D_6") (pintype "passive"))
      (node (ref "LED2") (pin "A") (pinfunction "A_A") (pintype "passive"))
      (node (ref "R9") (pin "1") (pinfunction "1_1") (pintype "passive"))
    )
    (net (code "30") (name "Net-(G4-G)") (class "Default")
      (node (ref "D11") (pin "A") (pinfunction "A_A") (pintype "passive"))
      (node (ref "G4") (pin "3") (pinfunction "G_3") (pintype "passive"))
      (node (ref "R14") (pin "2") (pinfunction "2_2") (pintype "passive"))
    )
    (net (code "31") (name "Net-(G4-S)") (class "Default")
      (node (ref "D11") (pin "C") (pinfunction "C_C") (pintype "passive"))
      (node (ref "G2") (pin "1") (pinfunction "D_1") (pintype "passive"))
      (node (ref "G2") (pin "2") (pinfunction "D_2") (pintype "passive"))
      (node (ref "G2") (pin "5") (pinfunction "D_5") (pintype "passive"))
      (node (ref "G2") (pin "6") (pinfunction "D_6") (pintype "passive"))
      (node (ref "G4") (pin "4") (pinfunction "S_4") (pintype "passive"))
      (node (ref "R11") (pin "2") (pinfunction "2_2") (pintype "passive"))
      (node (ref "R28") (pin "E") (pinfunction "E_E") (pintype "passive"))
      (node (ref "U5") (pin "5") (pinfunction "+VS_5") (pintype "input"))
    )
    (net (code "32") (name "Net-(JMP2-Pad2)") (class "Default")
      (node (ref "JMP2") (pin "2") (pinfunction "2_2") (pintype "passive"))
      (node (ref "R26") (pin "E") (pinfunction "E_E") (pintype "passive"))
    )
    (net (code "33") (name "Net-(JMP4-Pad2)") (class "Default")
      (node (ref "JMP4") (pin "2") (pinfunction "2_2") (pintype "passive"))
      (node (ref "R32") (pin "E") (pinfunction "E_E") (pintype "passive"))
    )
    (net (code "34") (name "Net-(JMP6-Pad2)") (class "Default")
      (node (ref "JMP6") (pin "2") (pinfunction "2_2") (pintype "passive"))
      (node (ref "R38") (pin "E") (pinfunction "E_E") (pintype "passive"))
    )
    (net (code "35") (name "Net-(JMP8-Pad2)") (class "Default")
      (node (ref "JMP8") (pin "2") (pinfunction "2_2") (pintype "passive"))
      (node (ref "R44") (pin "E") (pinfunction "E_E") (pintype "passive"))
    )
    (net (code "36") (name "Net-(JP1-Pad2)") (class "Default")
      (node (ref "JP1") (pin "2") (pinfunction "2_2") (pintype "passive"))
      (node (ref "R24") (pin "1") (pinfunction "1_1") (pintype "passive"))
      (node (ref "R25") (pin "2") (pinfunction "2_2") (pintype "passive"))
      (node (ref "R26") (pin "A") (pinfunction "A_A") (pintype "passive"))
    )
    (net (code "37") (name "Net-(JP2-Pad2)") (class "Default")
      (node (ref "JP2") (pin "2") (pinfunction "2_2") (pintype "passive"))
      (node (ref "R30") (pin "1") (pinfunction "1_1") (pintype "passive"))
      (node (ref "R31") (pin "2") (pinfunction "2_2") (pintype "passive"))
      (node (ref "R32") (pin "A") (pinfunction "A_A") (pintype "passive"))
    )
    (net (code "38") (name "Net-(JP3-Pad2)") (class "Default")
      (node (ref "JP3") (pin "2") (pinfunction "2_2") (pintype "passive"))
      (node (ref "R36") (pin "1") (pinfunction "1_1") (pintype "passive"))
      (node (ref "R37") (pin "2") (pinfunction "2_2") (pintype "passive"))
      (node (ref "R38") (pin "A") (pinfunction "A_A") (pintype "passive"))
    )
    (net (code "39") (name "Net-(JP4-Pad2)") (class "Default")
      (node (ref "JP4") (pin "2") (pinfunction "2_2") (pintype "passive"))
      (node (ref "R42") (pin "1") (pinfunction "1_1") (pintype "passive"))
      (node (ref "R43") (pin "2") (pinfunction "2_2") (pintype "passive"))
      (node (ref "R44") (pin "A") (pinfunction "A_A") (pintype "passive"))
    )
    (net (code "40") (name "Net-(JP5-Pad2)") (class "Default")
      (node (ref "JP5") (pin "2") (pinfunction "2_2") (pintype "passive"))
      (node (ref "R33") (pin "2") (pinfunction "2_2") (pintype "passive"))
    )
    (net (code "41") (name "Net-(LED1-PadC)") (class "Default")
      (node (ref "LED1") (pin "C") (pinfunction "C_C") (pintype "passive"))
      (node (ref "R16") (pin "2") (pinfunction "2_2") (pintype "passive"))
    )
    (net (code "42") (name "Net-(LED2-PadC)") (class "Default")
      (node (ref "LED2") (pin "C") (pinfunction "C_C") (pintype "passive"))
      (node (ref "R18") (pin "1") (pinfunction "1_1") (pintype "passive"))
    )
    (net (code "43") (name "Net-(LED3-PadC)") (class "Default")
      (node (ref "LED3") (pin "C") (pinfunction "C_C") (pintype "passive"))
      (node (ref "R17") (pin "2") (pinfunction "2_2") (pintype "passive"))
    )
    (net (code "44") (name "Net-(LED4-PadC)") (class "Default")
      (node (ref "LED4") (pin "C") (pinfunction "C_C") (pintype "passive"))
      (node (ref "R19") (pin "2") (pinfunction "2_2") (pintype "passive"))
    )
    (net (code "45") (name "Net-(M2-PadEN)") (class "Default")
      (node (ref "M2") (pin "EN") (pinfunction "EN_EN") (pintype "input"))
      (node (ref "R20") (pin "2") (pinfunction "2_2") (pintype "passive"))
    )
    (net (code "46") (name "Net-(S1-S)") (class "Default")
      (node (ref "S1") (pin "1") (pinfunction "S_1") (pintype "passive"))
      (node (ref "S1") (pin "2") (pinfunction "S1_2") (pintype "passive"))
      (node (ref "U1") (pin "7") (pinfunction "GPIO04_7") (pintype "bidirectional"))
    )
    (net (code "47") (name "Net-(U2-PA9)") (class "Default")
      (node (ref "R2") (pin "2") (pinfunction "2_2") (pintype "passive"))
      (node (ref "U2") (pin "P$6") (pinfunction "PA9_P$6") (pintype "bidirectional"))
    )
    (net (code "48") (name "Net-(U2-PA10)") (class "Default")
      (node (ref "R1") (pin "2") (pinfunction "2_2") (pintype "passive"))
      (node (ref "U2") (pin "P$7") (pinfunction "PA10_P$7") (pintype "bidirectional"))
    )
    (net (code "49") (name "Net-(U3-BS)") (class "Default")
      (node (ref "C4") (pin "1") (pinfunction "1_1") (pintype "passive"))
      (node (ref "U3") (pin "7") (pinfunction "BS_7") (pintype "bidirectional"))
    )
    (net (code "50") (name "Net-(U3-EN)") (class "Default")
      (node (ref "R35") (pin "1") (pinfunction "1_1") (pintype "passive"))
      (node (ref "U3") (pin "1") (pinfunction "EN_1") (pintype "bidirectional"))
    )
    (net (code "51") (name "Net-(U3-FB)") (class "Default")
      (node (ref "C3") (pin "2") (pinfunction "2_2") (pintype "passive"))
      (node (ref "R12") (pin "2") (pinfunction "2_2") (pintype "passive"))
      (node (ref "R13") (pin "1") (pinfunction "1_1") (pintype "passive"))
      (node (ref "U3") (pin "2") (pinfunction "FB_2") (pintype "bidirectional"))
    )
    (net (code "52") (name "Net-(U3-SS)") (class "Default")
      (node (ref "C1") (pin "1") (pinfunction "1_1") (pintype "passive"))
      (node (ref "U3") (pin "4") (pinfunction "SS_4") (pintype "bidirectional"))
    )
    (net (code "53") (name "Net-(U3-SW)") (class "Default")
      (node (ref "C4") (pin "2") (pinfunction "2_2") (pintype "passive"))
      (node (ref "L1") (pin "1") (pinfunction "1_1") (pintype "passive"))
      (node (ref "U3") (pin "6") (pinfunction "SW_6") (pintype "bidirectional"))
    )
    (net (code "54") (name "Net-(U3-VREG5)") (class "Default")
      (node (ref "C2") (pin "1") (pinfunction "1_1") (pintype "passive"))
      (node (ref "U3") (pin "3") (pinfunction "VREG5_3") (pintype "bidirectional"))
    )
    (net (code "55") (name "Net-(U5-IN+)") (class "Default")
      (node (ref "R15") (pin "1") (pinfunction "1_1") (pintype "passive"))
      (node (ref "R29") (pin "2") (pinfunction "2_2") (pintype "passive"))
      (node (ref "U5") (pin "1") (pinfunction "IN+_1") (pintype "input"))
    )
    (net (code "56") (name "Net-(U5-IN-)") (class "Default")
      (node (ref "R28") (pin "S") (pinfunction "S_S") (pintype "passive"))
      (node (ref "U5") (pin "3") (pinfunction "IN-_3") (pintype "input"))
    )
    (net (code "57") (name "Net-(U5-OUT)") (class "Default")
      (node (ref "LED3") (pin "A") (pinfunction "A_A") (pintype "passive"))
      (node (ref "R14") (pin "1") (pinfunction "1_1") (pintype "passive"))
      (node (ref "R29") (pin "1") (pinfunction "1_1") (pintype "passive"))
      (node (ref "U5") (pin "4") (pinfunction "OUT_4") (pintype "output"))
    )
    (net (code "58") (name "Net-(U7-FB)") (class "Default")
      (node (ref "R26") (pin "S") (pinfunction "S_S") (pintype "passive"))
      (node (ref "U7") (pin "3") (pinfunction "FB_3") (pintype "output"))
    )
    (net (code "59") (name "Net-(U7-OV)") (class "Default")
      (node (ref "C12") (pin "1") (pinfunction "1_1") (pintype "passive"))
      (node (ref "D12") (pin "C") (pinfunction "C_C") (pintype "passive"))
      (node (ref "JP1") (pin "1") (pinfunction "1_1") (pintype "passive"))
      (node (ref "U7") (pin "5") (pinfunction "OV_5") (pintype "passive"))
    )
    (net (code "60") (name "Net-(U7-SW)") (class "Default")
      (node (ref "D12") (pin "A") (pinfunction "A_A") (pintype "passive"))
      (node (ref "L3") (pin "2") (pinfunction "2_2") (pintype "passive"))
      (node (ref "U7") (pin "1") (pinfunction "SW_1") (pintype "output"))
    )
    (net (code "61") (name "Net-(U9-FB)") (class "Default")
      (node (ref "R32") (pin "S") (pinfunction "S_S") (pintype "passive"))
      (node (ref "U9") (pin "3") (pinfunction "FB_3") (pintype "output"))
    )
    (net (code "62") (name "Net-(U9-OV)") (class "Default")
      (node (ref "C16") (pin "1") (pinfunction "1_1") (pintype "passive"))
      (node (ref "D14") (pin "C") (pinfunction "C_C") (pintype "passive"))
      (node (ref "JP2") (pin "1") (pinfunction "1_1") (pintype "passive"))
      (node (ref "U9") (pin "5") (pinfunction "OV_5") (pintype "passive"))
    )
    (net (code "63") (name "Net-(U9-SW)") (class "Default")
      (node (ref "D14") (pin "A") (pinfunction "A_A") (pintype "passive"))
      (node (ref "L5") (pin "2") (pinfunction "2_2") (pintype "passive"))
      (node (ref "U9") (pin "1") (pinfunction "SW_1") (pintype "output"))
    )
    (net (code "64") (name "Net-(U11-FB)") (class "Default")
      (node (ref "R38") (pin "S") (pinfunction "S_S") (pintype "passive"))
      (node (ref "U11") (pin "3") (pinfunction "FB_3") (pintype "output"))
    )
    (net (code "65") (name "Net-(U11-OV)") (class "Default")
      (node (ref "C20") (pin "1") (pinfunction "1_1") (pintype "passive"))
      (node (ref "D16") (pin "C") (pinfunction "C_C") (pintype "passive"))
      (node (ref "JP3") (pin "1") (pinfunction "1_1") (pintype "passive"))
      (node (ref "U11") (pin "5") (pinfunction "OV_5") (pintype "passive"))
    )
    (net (code "66") (name "Net-(U11-SW)") (class "Default")
      (node (ref "D16") (pin "A") (pinfunction "A_A") (pintype "passive"))
      (node (ref "L7") (pin "2") (pinfunction "2_2") (pintype "passive"))
      (node (ref "U11") (pin "1") (pinfunction "SW_1") (pintype "output"))
    )
    (net (code "67") (name "Net-(U13-FB)") (class "Default")
      (node (ref "R44") (pin "S") (pinfunction "S_S") (pintype "passive"))
      (node (ref "U13") (pin "3") (pinfunction "FB_3") (pintype "output"))
    )
    (net (code "68") (name "Net-(U13-OV)") (class "Default")
      (node (ref "C24") (pin "1") (pinfunction "1_1") (pintype "passive"))
      (node (ref "D18") (pin "C") (pinfunction "C_C") (pintype "passive"))
      (node (ref "JP4") (pin "1") (pinfunction "1_1") (pintype "passive"))
      (node (ref "U13") (pin "5") (pinfunction "OV_5") (pintype "passive"))
    )
    (net (code "69") (name "Net-(U13-SW)") (class "Default")
      (node (ref "D18") (pin "A") (pinfunction "A_A") (pintype "passive"))
      (node (ref "L9") (pin "2") (pinfunction "2_2") (pintype "passive"))
      (node (ref "U13") (pin "1") (pinfunction "SW_1") (pintype "output"))
    )
    (net (code "70") (name "RF_INT") (class "Default")
      (node (ref "M1") (pin "8") (pinfunction "IRQ_8") (pintype "bidirectional"))
      (node (ref "U2") (pin "P$13") (pinfunction "PB5_P$13") (pintype "bidirectional"))
    )
    (net (code "71") (name "RIGHT_BTN") (class "Default")
      (node (ref "J3") (pin "5") (pinfunction "5_5") (pintype "passive"))
      (node (ref "U2") (pin "P$4") (pinfunction "PB15_P$4") (pintype "bidirectional"))
    )
    (net (code "72") (name "RIGHT_CTRL") (class "Default")
      (node (ref "R27") (pin "1") (pinfunction "1_1") (pintype "passive"))
      (node (ref "U13") (pin "4") (pinfunction "CTRL_4") (pintype "passive"))
      (node (ref "U2") (pin "P$17") (pinfunction "PB9_P$17") (pintype "bidirectional"))
    )
    (net (code "73") (name "TAIL_BTN") (class "Default")
      (node (ref "J3") (pin "3") (pinfunction "3_3") (pintype "passive"))
      (node (ref "U2") (pin "P$2") (pinfunction "PB13_P$2") (pintype "bidirectional"))
    )
    (net (code "74") (name "TAIL_CTRL") (class "Default")
      (node (ref "R22") (pin "1") (pinfunction "1_1") (pintype "passive"))
      (node (ref "U2") (pin "P$15") (pinfunction "PB7_P$15") (pintype "bidirectional"))
      (node (ref "U9") (pin "4") (pinfunction "CTRL_4") (pintype "passive"))
    )
    (net (code "75") (name "V+") (class "Default")
      (node (ref "C11") (pin "1") (pinfunction "1_1") (pintype "passive"))
      (node (ref "C15") (pin "1") (pinfunction "1_1") (pintype "passive"))
      (node (ref "C19") (pin "1") (pinfunction "1_1") (pintype "passive"))
      (node (ref "C23") (pin "1") (pinfunction "1_1") (pintype "passive"))
      (node (ref "C7") (pin "1") (pinfunction "1_1") (pintype "passive"))
      (node (ref "C8") (pin "1") (pinfunction "1_1") (pintype "passive"))
      (node (ref "G4") (pin "1") (pinfunction "D_1") (pintype "passive"))
      (node (ref "G4") (pin "2") (pinfunction "D_2") (pintype "passive"))
      (node (ref "G4") (pin "5") (pinfunction "D_5") (pintype "passive"))
      (node (ref "G4") (pin "6") (pinfunction "D_6") (pintype "passive"))
      (node (ref "J5") (pin "1") (pinfunction "1_1") (pintype "passive"))
      (node (ref "JMP2") (pin "1") (pinfunction "1_1") (pintype "passive"))
      (node (ref "JMP4") (pin "1") (pinfunction "1_1") (pintype "passive"))
      (node (ref "JMP6") (pin "1") (pinfunction "1_1") (pintype "passive"))
      (node (ref "JMP8") (pin "1") (pinfunction "1_1") (pintype "passive"))
      (node (ref "L3") (pin "1") (pinfunction "1_1") (pintype "passive"))
      (node (ref "L5") (pin "1") (pinfunction "1_1") (pintype "passive"))
      (node (ref "L7") (pin "1") (pinfunction "1_1") (pintype "passive"))
      (node (ref "L9") (pin "1") (pinfunction "1_1") (pintype "passive"))
      (node (ref "R35") (pin "2") (pinfunction "2_2") (pintype "passive"))
      (node (ref "R6") (pin "2") (pinfunction "2_2") (pintype "passive"))
      (node (ref "TP2") (pin "TP") (pinfunction "TP_TP") (pintype "input"))
      (node (ref "U11") (pin "6") (pinfunction "VIN_6") (pintype "input"))
      (node (ref "U13") (pin "6") (pinfunction "VIN_6") (pintype "input"))
      (node (ref "U3") (pin "8") (pinfunction "VIN_8") (pintype "bidirectional"))
      (node (ref "U7") (pin "6") (pinfunction "VIN_6") (pintype "input"))
      (node (ref "U9") (pin "6") (pinfunction "VIN_6") (pintype "input"))
    )
    (net (code "76") (name "VCC") (class "Default")
      (node (ref "D10") (pin "C") (pinfunction "C_C") (pintype "passive"))
      (node (ref "G1") (pin "1") (pinfunction "D_1") (pintype "passive"))
      (node (ref "G1") (pin "2") (pinfunction "D_2") (pintype "passive"))
      (node (ref "G1") (pin "5") (pinfunction "D_5") (pintype "passive"))
      (node (ref "G1") (pin "6") (pinfunction "D_6") (pintype "passive"))
      (node (ref "J1") (pin "2") (pinfunction "1_2") (pintype "passive"))
    )
    (net (code "77") (name "unconnected-(M2-3V3-Pad3V3OUT)") (class "Default")
      (node (ref "M2") (pin "3V3OUT") (pinfunction "3V3_3V3OUT") (pintype "output"))
    )
    (net (code "78") (name "unconnected-(M2-PadFIX)") (class "Default")
      (node (ref "M2") (pin "FIX") (pinfunction "FIX_FIX") (pintype "output"))
    )
    (net (code "79") (name "unconnected-(M2-PadPPS)") (class "Default")
      (node (ref "M2") (pin "PPS") (pinfunction "PPS_PPS") (pintype "output"))
    )
    (net (code "80") (name "unconnected-(M2-PadVBAT)") (class "Default")
      (node (ref "M2") (pin "VBAT") (pinfunction "VBAT_VBAT") (pintype "bidirectional"))
    )
    (net (code "81") (name "unconnected-(U1-GPIO05-Pad29)") (class "Default")
      (node (ref "U1") (pin "29") (pinfunction "GPIO05_29") (pintype "bidirectional"))
    )
    (net (code "82") (name "unconnected-(U1-GPIO06-Pad31)") (class "Default")
      (node (ref "U1") (pin "31") (pinfunction "GPIO06_31") (pintype "bidirectional"))
    )
    (net (code "83") (name "unconnected-(U1-GPIO12-Pad32)") (class "Default")
      (node (ref "U1") (pin "32") (pinfunction "GPIO12_32") (pintype "bidirectional"))
    )
    (net (code "84") (name "unconnected-(U1-GPIO13-Pad33)") (class "Default")
      (node (ref "U1") (pin "33") (pinfunction "GPIO13_33") (pintype "bidirectional"))
    )
    (net (code "85") (name "unconnected-(U1-GPIO16-Pad36)") (class "Default")
      (node (ref "U1") (pin "36") (pinfunction "GPIO16_36") (pintype "bidirectional"))
    )
    (net (code "86") (name "unconnected-(U1-GPIO17-Pad11)") (class "Default")
      (node (ref "U1") (pin "11") (pinfunction "GPIO17_11") (pintype "bidirectional"))
    )
    (net (code "87") (name "unconnected-(U1-GPIO18-Pad12)") (class "Default")
      (node (ref "U1") (pin "12") (pinfunction "GPIO18_12") (pintype "bidirectional"))
    )
    (net (code "88") (name "unconnected-(U1-GPIO19-Pad35)") (class "Default")
      (node (ref "U1") (pin "35") (pinfunction "GPIO19_35") (pintype "bidirectional"))
    )
    (net (code "89") (name "unconnected-(U1-GPIO20-Pad38)") (class "Default")
      (node (ref "U1") (pin "38") (pinfunction "GPIO20_38") (pintype "bidirectional"))
    )
    (net (code "90") (name "unconnected-(U1-GPIO21-Pad40)") (class "Default")
      (node (ref "U1") (pin "40") (pinfunction "GPIO21_40") (pintype "bidirectional"))
    )
    (net (code "91") (name "unconnected-(U1-GPIO22-Pad15)") (class "Default")
      (node (ref "U1") (pin "15") (pinfunction "GPIO22_15") (pintype "bidirectional"))
    )
    (net (code "92") (name "unconnected-(U1-GPIO23-Pad16)") (class "Default")
      (node (ref "U1") (pin "16") (pinfunction "GPIO23_16") (pintype "bidirectional"))
    )
    (net (code "93") (name "unconnected-(U1-GPIO24-Pad18)") (class "Default")
      (node (ref "U1") (pin "18") (pinfunction "GPIO24_18") (pintype "bidirectional"))
    )
    (net (code "94") (name "unconnected-(U1-GPIO25-Pad22)") (class "Default")
      (node (ref "U1") (pin "22") (pinfunction "GPIO25_22") (pintype "bidirectional"))
    )
    (net (code "95") (name "unconnected-(U1-GPIO26-Pad37)") (class "Default")
      (node (ref "U1") (pin "37") (pinfunction "GPIO26_37") (pintype "bidirectional"))
    )
    (net (code "96") (name "unconnected-(U1-GPIO27-Pad13)") (class "Default")
      (node (ref "U1") (pin "13") (pinfunction "GPIO27_13") (pintype "bidirectional"))
    )
    (net (code "97") (name "unconnected-(U1-ID_SC-Pad28)") (class "Default")
      (node (ref "U1") (pin "28") (pinfunction "ID_SC_28") (pintype "no_connect"))
    )
    (net (code "98") (name "unconnected-(U1-ID_SD-Pad27)") (class "Default")
      (node (ref "U1") (pin "27") (pinfunction "ID_SD_27") (pintype "no_connect"))
    )
    (net (code "99") (name "unconnected-(U1-SCL-Pad5)") (class "Default")
      (node (ref "U1") (pin "5") (pinfunction "SCL_5") (pintype "bidirectional"))
    )
    (net (code "100") (name "unconnected-(U1-SDA-Pad3)") (class "Default")
      (node (ref "U1") (pin "3") (pinfunction "SDA_3") (pintype "bidirectional"))
    )
    (net (code "101") (name "unconnected-(U1-SPI_CE0-Pad24)") (class "Default")
      (node (ref "U1") (pin "24") (pinfunction "SPI_CE0_24") (pintype "bidirectional"))
    )
    (net (code "102") (name "unconnected-(U1-SPI_CE1-Pad26)") (class "Default")
      (node (ref "U1") (pin "26") (pinfunction "SPI_CE1_26") (pintype "bidirectional"))
    )
    (net (code "103") (name "unconnected-(U1-SPI_MISO-Pad21)") (class "Default")
      (node (ref "U1") (pin "21") (pinfunction "SPI_MISO_21") (pintype "bidirectional"))
    )
    (net (code "104") (name "unconnected-(U1-SPI_MOSI-Pad19)") (class "Default")
      (node (ref "U1") (pin "19") (pinfunction "SPI_MOSI_19") (pintype "bidirectional"))
    )
    (net (code "105") (name "unconnected-(U1-SPI_SCLK-Pad23)") (class "Default")
      (node (ref "U1") (pin "23") (pinfunction "SPI_SCLK_23") (pintype "bidirectional"))
    )
    (net (code "106") (name "unconnected-(U2-5V-PadP$18)") (class "Default")
      (node (ref "U2") (pin "P$18") (pinfunction "5V_P$18") (pintype "bidirectional"))
    )
    (net (code "107") (name "unconnected-(U2-PA8-PadP$5)") (class "Default")
      (node (ref "U2") (pin "P$5") (pinfunction "PA8_P$5") (pintype "bidirectional"))
    )
    (net (code "108") (name "unconnected-(U2-PA11-PadP$8)") (class "Default")
      (node (ref "U2") (pin "P$8") (pinfunction "PA11_P$8") (pintype "bidirectional"))
    )
    (net (code "109") (name "unconnected-(U2-PA12-PadP$9)") (class "Default")
      (node (ref "U2") (pin "P$9") (pinfunction "PA12_P$9") (pintype "bidirectional"))
    )
    (net (code "110") (name "unconnected-(U2-PB1-PadP$27)") (class "Default")
      (node (ref "U2") (pin "P$27") (pinfunction "PB1_P$27") (pintype "bidirectional"))
    )
    (net (code "111") (name "unconnected-(U2-PB10-PadP$26)") (class "Default")
      (node (ref "U2") (pin "P$26") (pinfunction "PB10_P$26") (pintype "bidirectional"))
    )
    (net (code "112") (name "unconnected-(U2-PB11-PadP$25)") (class "Default")
      (node (ref "U2") (pin "P$25") (pinfunction "PB11_P$25") (pintype "bidirectional"))
    )
    (net (code "113") (name "unconnected-(U2-PC13-PadP$39)") (class "Default")
      (node (ref "U2") (pin "P$39") (pinfunction "PC13_P$39") (pintype "bidirectional"))
    )
    (net (code "114") (name "unconnected-(U2-PC14-PadP$38)") (class "Default")
      (node (ref "U2") (pin "P$38") (pinfunction "PC14_P$38") (pintype "bidirectional"))
    )
    (net (code "115") (name "unconnected-(U2-PC15-PadP$37)") (class "Default")
      (node (ref "U2") (pin "P$37") (pinfunction "PC15_P$37") (pintype "bidirectional"))
    )
    (net (code "116") (name "unconnected-(U2-RESET-PadP$24)") (class "Default")
      (node (ref "U2") (pin "P$24") (pinfunction "RESET_P$24") (pintype "bidirectional"))
    )
    (net (code "117") (name "unconnected-(U2-VBAT-PadP$40)") (class "Default")
      (node (ref "U2") (pin "P$40") (pinfunction "VBAT_P$40") (pintype "bidirectional"))
    )
    (net (code "118") (name "unconnected-(U4-N.C.-Pad3)") (class "Default")
      (node (ref "U4") (pin "3") (pinfunction "N.C._3") (pintype "passive"))
    )
  )
)
